# Output.net
KiCad netlist of a schematic drawn in Altium Designer
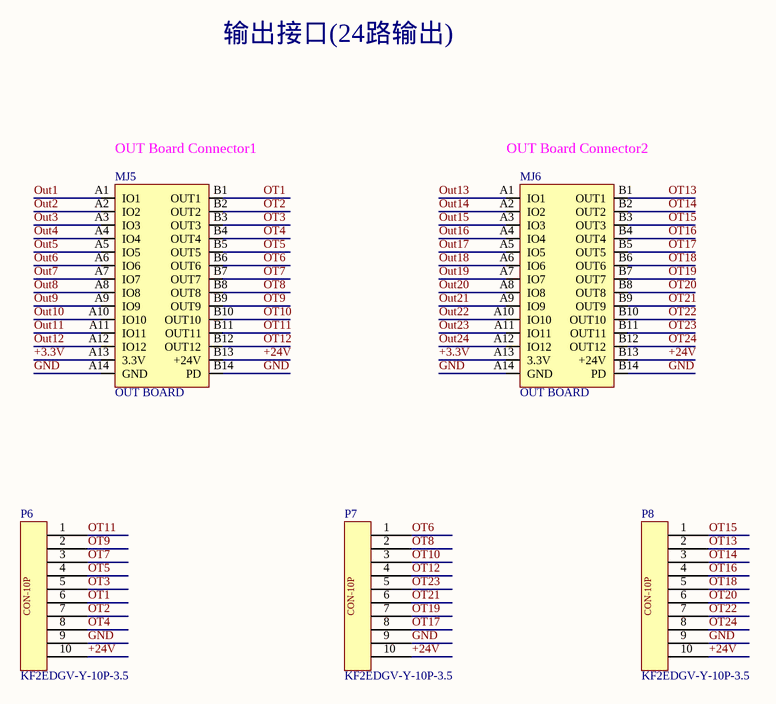
[diagram p0: Output.SchDoc]

(export (version "E")
  (design (tool "Eeschema 10.0.6"))
  (components
    (comp (ref "MJ5")
      (value "OUT BOARD")
      (footprint "OUT BOARD")
      (libsource (lib "Block Board Library SCH") (part "J-OUTPUT"))
    )
    (comp (ref "MJ6")
      (value "OUT BOARD")
      (footprint "OUT BOARD")
      (libsource (lib "Block Board Library SCH") (part "J-OUTPUT"))
    )
    (comp (ref "P6")
      (value "KF2EDGV-Y-10P-3.5")
      (footprint "KF2EDGV-Y-10P-3.5")
      (libsource (lib "Next_SCHlib") (part "CON-10P"))
    )
    (comp (ref "P7")
      (value "KF2EDGV-Y-10P-3.5")
      (footprint "KF2EDGV-Y-10P-3.5")
      (libsource (lib "Next_SCHlib") (part "CON-10P"))
    )
    (comp (ref "P8")
      (value "KF2EDGV-Y-10P-3.5")
      (footprint "KF2EDGV-Y-10P-3.5")
      (libsource (lib "Next_SCHlib") (part "CON-10P"))
    )
  )
  (nets
    (net (code "1") (name "/+3.3V") (class "Default")
      (node (ref "MJ5") (pin "A13") (pinfunction "3.3V_A13") (pintype "passive"))
      (node (ref "MJ6") (pin "A13") (pinfunction "3.3V_A13") (pintype "passive"))
    )
    (net (code "2") (name "/+24V") (class "Default")
      (node (ref "MJ5") (pin "B13") (pinfunction "+24V_B13") (pintype "passive"))
      (node (ref "MJ6") (pin "B13") (pinfunction "+24V_B13") (pintype "passive"))
      (node (ref "P6") (pin "10") (pinfunction "10_10") (pintype "passive"))
      (node (ref "P7") (pin "10") (pinfunction "10_10") (pintype "passive"))
      (node (ref "P8") (pin "10") (pinfunction "10_10") (pintype "passive"))
    )
    (net (code "3") (name "/GND") (class "Default")
      (node (ref "MJ5") (pin "A14") (pinfunction "GND_A14") (pintype "passive"))
      (node (ref "MJ5") (pin "B14") (pinfunction "PD_B14") (pintype "passive"))
      (node (ref "MJ6") (pin "A14") (pinfunction "GND_A14") (pintype "passive"))
      (node (ref "MJ6") (pin "B14") (pinfunction "PD_B14") (pintype "passive"))
      (node (ref "P6") (pin "9") (pinfunction "9_9") (pintype "passive"))
      (node (ref "P7") (pin "9") (pinfunction "9_9") (pintype "passive"))
      (node (ref "P8") (pin "9") (pinfunction "9_9") (pintype "passive"))
    )
    (net (code "4") (name "/OT1") (class "Default")
      (node (ref "MJ5") (pin "B1") (pinfunction "OUT1_B1") (pintype "passive"))
      (node (ref "P6") (pin "6") (pinfunction "6_6") (pintype "passive"))
    )
    (net (code "5") (name "/OT2") (class "Default")
      (node (ref "MJ5") (pin "B2") (pinfunction "OUT2_B2") (pintype "passive"))
      (node (ref "P6") (pin "7") (pinfunction "7_7") (pintype "passive"))
    )
    (net (code "6") (name "/OT3") (class "Default")
      (node (ref "MJ5") (pin "B3") (pinfunction "OUT3_B3") (pintype "passive"))
      (node (ref "P6") (pin "5") (pinfunction "5_5") (pintype "passive"))
    )
    (net (code "7") (name "/OT4") (class "Default")
      (node (ref "MJ5") (pin "B4") (pinfunction "OUT4_B4") (pintype "passive"))
      (node (ref "P6") (pin "8") (pinfunction "8_8") (pintype "passive"))
    )
    (net (code "8") (name "/OT5") (class "Default")
      (node (ref "MJ5") (pin "B5") (pinfunction "OUT5_B5") (pintype "passive"))
      (node (ref "P6") (pin "4") (pinfunction "4_4") (pintype "passive"))
    )
    (net (code "9") (name "/OT6") (class "Default")
      (node (ref "MJ5") (pin "B6") (pinfunction "OUT6_B6") (pintype "passive"))
      (node (ref "P7") (pin "1") (pinfunction "1_1") (pintype "passive"))
    )
    (net (code "10") (name "/OT7") (class "Default")
      (node (ref "MJ5") (pin "B7") (pinfunction "OUT7_B7") (pintype "passive"))
      (node (ref "P6") (pin "3") (pinfunction "3_3") (pintype "passive"))
    )
    (net (code "11") (name "/OT8") (class "Default")
      (node (ref "MJ5") (pin "B8") (pinfunction "OUT8_B8") (pintype "passive"))
      (node (ref "P7") (pin "2") (pinfunction "2_2") (pintype "passive"))
    )
    (net (code "12") (name "/OT9") (class "Default")
      (node (ref "MJ5") (pin "B9") (pinfunction "OUT9_B9") (pintype "passive"))
      (node (ref "P6") (pin "2") (pinfunction "2_2") (pintype "passive"))
    )
    (net (code "13") (name "/OT10") (class "Default")
      (node (ref "MJ5") (pin "B10") (pinfunction "OUT10_B10") (pintype "passive"))
      (node (ref "P7") (pin "3") (pinfunction "3_3") (pintype "passive"))
    )
    (net (code "14") (name "/OT11") (class "Default")
      (node (ref "MJ5") (pin "B11") (pinfunction "OUT11_B11") (pintype "passive"))
      (node (ref "P6") (pin "1") (pinfunction "1_1") (pintype "passive"))
    )
    (net (code "15") (name "/OT12") (class "Default")
      (node (ref "MJ5") (pin "B12") (pinfunction "OUT12_B12") (pintype "passive"))
      (node (ref "P7") (pin "4") (pinfunction "4_4") (pintype "passive"))
    )
    (net (code "16") (name "/OT13") (class "Default")
      (node (ref "MJ6") (pin "B1") (pinfunction "OUT1_B1") (pintype "passive"))
      (node (ref "P8") (pin "2") (pinfunction "2_2") (pintype "passive"))
    )
    (net (code "17") (name "/OT14") (class "Default")
      (node (ref "MJ6") (pin "B2") (pinfunction "OUT2_B2") (pintype "passive"))
      (node (ref "P8") (pin "3") (pinfunction "3_3") (pintype "passive"))
    )
    (net (code "18") (name "/OT15") (class "Default")
      (node (ref "MJ6") (pin "B3") (pinfunction "OUT3_B3") (pintype "passive"))
      (node (ref "P8") (pin "1") (pinfunction "1_1") (pintype "passive"))
    )
    (net (code "19") (name "/OT16") (class "Default")
      (node (ref "MJ6") (pin "B4") (pinfunction "OUT4_B4") (pintype "passive"))
      (node (ref "P8") (pin "4") (pinfunction "4_4") (pintype "passive"))
    )
    (net (code "20") (name "/OT17") (class "Default")
      (node (ref "MJ6") (pin "B5") (pinfunction "OUT5_B5") (pintype "passive"))
      (node (ref "P7") (pin "8") (pinfunction "8_8") (pintype "passive"))
    )
    (net (code "21") (name "/OT18") (class "Default")
      (node (ref "MJ6") (pin "B6") (pinfunction "OUT6_B6") (pintype "passive"))
      (node (ref "P8") (pin "5") (pinfunction "5_5") (pintype "passive"))
    )
    (net (code "22") (name "/OT19") (class "Default")
      (node (ref "MJ6") (pin "B7") (pinfunction "OUT7_B7") (pintype "passive"))
      (node (ref "P7") (pin "7") (pinfunction "7_7") (pintype "passive"))
    )
    (net (code "23") (name "/OT20") (class "Default")
      (node (ref "MJ6") (pin "B8") (pinfunction "OUT8_B8") (pintype "passive"))
      (node (ref "P8") (pin "6") (pinfunction "6_6") (pintype "passive"))
    )
    (net (code "24") (name "/OT21") (class "Default")
      (node (ref "MJ6") (pin "B9") (pinfunction "OUT9_B9") (pintype "passive"))
      (node (ref "P7") (pin "6") (pinfunction "6_6") (pintype "passive"))
    )
    (net (code "25") (name "/OT22") (class "Default")
      (node (ref "MJ6") (pin "B10") (pinfunction "OUT10_B10") (pintype "passive"))
      (node (ref "P8") (pin "7") (pinfunction "7_7") (pintype "passive"))
    )
    (net (code "26") (name "/OT23") (class "Default")
      (node (ref "MJ6") (pin "B11") (pinfunction "OUT11_B11") (pintype "passive"))
      (node (ref "P7") (pin "5") (pinfunction "5_5") (pintype "passive"))
    )
    (net (code "27") (name "/OT24") (class "Default")
      (node (ref "MJ6") (pin "B12") (pinfunction "OUT12_B12") (pintype "passive"))
      (node (ref "P8") (pin "8") (pinfunction "8_8") (pintype "passive"))
    )
    (net (code "28") (name "/Out1") (class "Default")
      (node (ref "MJ5") (pin "A1") (pinfunction "IO1_A1") (pintype "passive"))
    )
    (net (code "29") (name "/Out2") (class "Default")
      (node (ref "MJ5") (pin "A2") (pinfunction "IO2_A2") (pintype "passive"))
    )
    (net (code "30") (name "/Out3") (class "Default")
      (node (ref "MJ5") (pin "A3") (pinfunction "IO3_A3") (pintype "passive"))
    )
    (net (code "31") (name "/Out4") (class "Default")
      (node (ref "MJ5") (pin "A4") (pinfunction "IO4_A4") (pintype "passive"))
    )
    (net (code "32") (name "/Out5") (class "Default")
      (node (ref "MJ5") (pin "A5") (pinfunction "IO5_A5") (pintype "passive"))
    )
    (net (code "33") (name "/Out6") (class "Default")
      (node (ref "MJ5") (pin "A6") (pinfunction "IO6_A6") (pintype "passive"))
    )
    (net (code "34") (name "/Out7") (class "Default")
      (node (ref "MJ5") (pin "A7") (pinfunction "IO7_A7") (pintype "passive"))
    )
    (net (code "35") (name "/Out8") (class "Default")
      (node (ref "MJ5") (pin "A8") (pinfunction "IO8_A8") (pintype "passive"))
    )
    (net (code "36") (name "/Out9") (class "Default")
      (node (ref "MJ5") (pin "A9") (pinfunction "IO9_A9") (pintype "passive"))
    )
    (net (code "37") (name "/Out10") (class "Default")
      (node (ref "MJ5") (pin "A10") (pinfunction "IO10_A10") (pintype "passive"))
    )
    (net (code "38") (name "/Out11") (class "Default")
      (node (ref "MJ5") (pin "A11") (pinfunction "IO11_A11") (pintype "passive"))
    )
    (net (code "39") (name "/Out12") (class "Default")
      (node (ref "MJ5") (pin "A12") (pinfunction "IO12_A12") (pintype "passive"))
    )
    (net (code "40") (name "/Out13") (class "Default")
      (node (ref "MJ6") (pin "A1") (pinfunction "IO1_A1") (pintype "passive"))
    )
    (net (code "41") (name "/Out14") (class "Default")
      (node (ref "MJ6") (pin "A2") (pinfunction "IO2_A2") (pintype "passive"))
    )
    (net (code "42") (name "/Out15") (class "Default")
      (node (ref "MJ6") (pin "A3") (pinfunction "IO3_A3") (pintype "passive"))
    )
    (net (code "43") (name "/Out16") (class "Default")
      (node (ref "MJ6") (pin "A4") (pinfunction "IO4_A4") (pintype "passive"))
    )
    (net (code "44") (name "/Out17") (class "Default")
      (node (ref "MJ6") (pin "A5") (pinfunction "IO5_A5") (pintype "passive"))
    )
    (net (code "45") (name "/Out18") (class "Default")
      (node (ref "MJ6") (pin "A6") (pinfunction "IO6_A6") (pintype "passive"))
    )
    (net (code "46") (name "/Out19") (class "Default")
      (node (ref "MJ6") (pin "A7") (pinfunction "IO7_A7") (pintype "passive"))
    )
    (net (code "47") (name "/Out20") (class "Default")
      (node (ref "MJ6") (pin "A8") (pinfunction "IO8_A8") (pintype "passive"))
    )
    (net (code "48") (name "/Out21") (class "Default")
      (node (ref "MJ6") (pin "A9") (pinfunction "IO9_A9") (pintype "passive"))
    )
    (net (code "49") (name "/Out22") (class "Default")
      (node (ref "MJ6") (pin "A10") (pinfunction "IO10_A10") (pintype "passive"))
    )
    (net (code "50") (name "/Out23") (class "Default")
      (node (ref "MJ6") (pin "A11") (pinfunction "IO11_A11") (pintype "passive"))
    )
    (net (code "51") (name "/Out24") (class "Default")
      (node (ref "MJ6") (pin "A12") (pinfunction "IO12_A12") (pintype "passive"))
    )
  )
)
